# pinky_2_micro_resistors.net
KiCad netlist of a schematic drawn in EAGLE
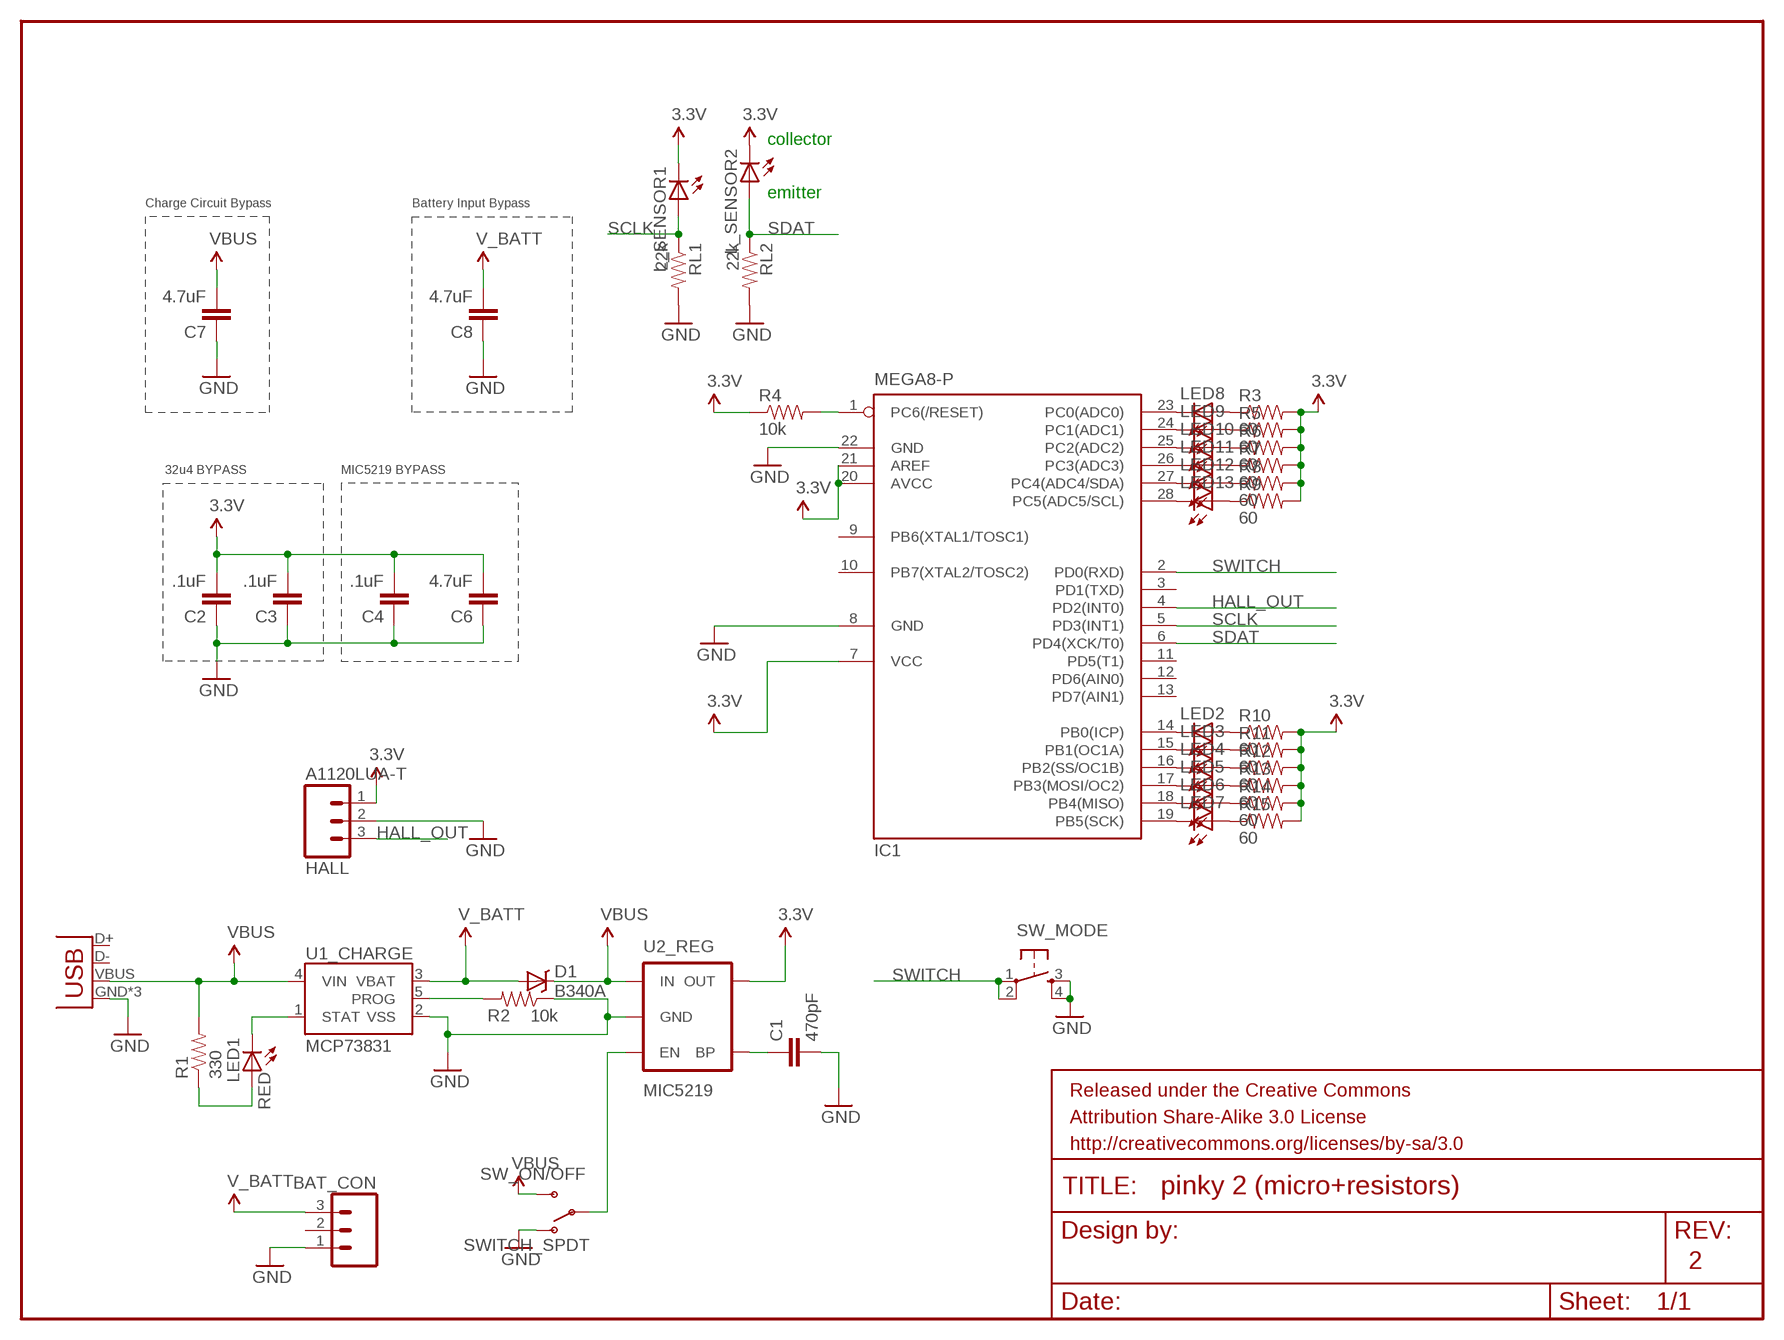
[diagram p0: schematic, sheet 1]

(export (version "E")
  (design (tool "Eeschema 10.0.6"))
  (components
    (comp (ref "BAT_CON")
      (value "M03PTH")
      (footprint "eagle-import:1X03")
      (libsource (lib "eagle-import") (part "M03PTH"))
    )
    (comp (ref "C1")
      (value "470pF")
      (footprint "eagle-import:1206")
      (libsource (lib "eagle-import") (part "CAP1206"))
    )
    (comp (ref "C2")
      (value ".1uF")
      (footprint "eagle-import:1206")
      (libsource (lib "eagle-import") (part "CAP1206"))
    )
    (comp (ref "C3")
      (value ".1uF")
      (footprint "eagle-import:1206")
      (libsource (lib "eagle-import") (part "CAP1206"))
    )
    (comp (ref "C4")
      (value ".1uF")
      (footprint "eagle-import:1206")
      (libsource (lib "eagle-import") (part "CAP1206"))
    )
    (comp (ref "C6")
      (value "4.7uF")
      (footprint "eagle-import:1206")
      (libsource (lib "eagle-import") (part "CAP1206"))
    )
    (comp (ref "C7")
      (value "4.7uF")
      (footprint "eagle-import:1206")
      (libsource (lib "eagle-import") (part "CAP1206"))
    )
    (comp (ref "C8")
      (value "4.7uF")
      (footprint "eagle-import:1206")
      (libsource (lib "eagle-import") (part "CAP1206"))
    )
    (comp (ref "D1")
      (value "B340A")
      (footprint "eagle-import:SMA-DIODE")
      (libsource (lib "eagle-import") (part "DIODE-SCHOTTKY_"))
    )
    (comp (ref "HALL")
      (value "A1120LUA-T")
      (footprint "eagle-import:1X03")
      (libsource (lib "eagle-import") (part "M03PTH"))
    )
    (comp (ref "IC1")
      (value "MEGA8-P")
      (footprint "eagle-import:DIL28-3")
      (libsource (lib "eagle-import") (part "MEGA8-P"))
    )
    (comp (ref "LED1")
      (value "RED")
      (footprint "eagle-import:LED-1206")
      (libsource (lib "eagle-import") (part "LED1206"))
    )
    (comp (ref "LED2")
      (value "LED1206")
      (footprint "eagle-import:LED-1206")
      (libsource (lib "eagle-import") (part "LED1206"))
    )
    (comp (ref "LED3")
      (value "LED1206")
      (footprint "eagle-import:LED-1206")
      (libsource (lib "eagle-import") (part "LED1206"))
    )
    (comp (ref "LED4")
      (value "LED1206")
      (footprint "eagle-import:LED-1206")
      (libsource (lib "eagle-import") (part "LED1206"))
    )
    (comp (ref "LED5")
      (value "LED1206")
      (footprint "eagle-import:LED-1206")
      (libsource (lib "eagle-import") (part "LED1206"))
    )
    (comp (ref "LED6")
      (value "LED1206")
      (footprint "eagle-import:LED-1206")
      (libsource (lib "eagle-import") (part "LED1206"))
    )
    (comp (ref "LED7")
      (value "LED1206")
      (footprint "eagle-import:LED-1206")
      (libsource (lib "eagle-import") (part "LED1206"))
    )
    (comp (ref "LED8")
      (value "LED1206")
      (footprint "eagle-import:LED-1206")
      (libsource (lib "eagle-import") (part "LED1206"))
    )
    (comp (ref "LED9")
      (value "LED1206")
      (footprint "eagle-import:LED-1206")
      (libsource (lib "eagle-import") (part "LED1206"))
    )
    (comp (ref "LED10")
      (value "LED1206")
      (footprint "eagle-import:LED-1206")
      (libsource (lib "eagle-import") (part "LED1206"))
    )
    (comp (ref "LED11")
      (value "LED1206")
      (footprint "eagle-import:LED-1206")
      (libsource (lib "eagle-import") (part "LED1206"))
    )
    (comp (ref "LED12")
      (value "LED1206")
      (footprint "eagle-import:LED-1206")
      (libsource (lib "eagle-import") (part "LED1206"))
    )
    (comp (ref "LED13")
      (value "LED1206")
      (footprint "eagle-import:LED-1206")
      (libsource (lib "eagle-import") (part "LED1206"))
    )
    (comp (ref "L_SENSOR1")
      (value "LED3MM")
      (footprint "eagle-import:LED3MM")
      (libsource (lib "eagle-import") (part "LED3MM"))
    )
    (comp (ref "L_SENSOR2")
      (value "LED3MM")
      (footprint "eagle-import:LED3MM")
      (libsource (lib "eagle-import") (part "LED3MM"))
    )
    (comp (ref "R1")
      (value "330")
      (footprint "eagle-import:1206")
      (libsource (lib "eagle-import") (part "RESISTOR1206"))
    )
    (comp (ref "R2")
      (value "10k")
      (footprint "eagle-import:1206")
      (libsource (lib "eagle-import") (part "RESISTOR1206"))
    )
    (comp (ref "R3")
      (value "60")
      (footprint "eagle-import:1206")
      (libsource (lib "eagle-import") (part "RESISTOR1206"))
    )
    (comp (ref "R4")
      (value "10k")
      (footprint "eagle-import:1206")
      (libsource (lib "eagle-import") (part "RESISTOR1206"))
    )
    (comp (ref "R5")
      (value "60")
      (footprint "eagle-import:1206")
      (libsource (lib "eagle-import") (part "RESISTOR1206"))
    )
    (comp (ref "R6")
      (value "60")
      (footprint "eagle-import:1206")
      (libsource (lib "eagle-import") (part "RESISTOR1206"))
    )
    (comp (ref "R7")
      (value "60")
      (footprint "eagle-import:1206")
      (libsource (lib "eagle-import") (part "RESISTOR1206"))
    )
    (comp (ref "R8")
      (value "60")
      (footprint "eagle-import:1206")
      (libsource (lib "eagle-import") (part "RESISTOR1206"))
    )
    (comp (ref "R9")
      (value "60")
      (footprint "eagle-import:1206")
      (libsource (lib "eagle-import") (part "RESISTOR1206"))
    )
    (comp (ref "R10")
      (value "60")
      (footprint "eagle-import:1206")
      (libsource (lib "eagle-import") (part "RESISTOR1206"))
    )
    (comp (ref "R11")
      (value "60")
      (footprint "eagle-import:1206")
      (libsource (lib "eagle-import") (part "RESISTOR1206"))
    )
    (comp (ref "R12")
      (value "60")
      (footprint "eagle-import:1206")
      (libsource (lib "eagle-import") (part "RESISTOR1206"))
    )
    (comp (ref "R13")
      (value "60")
      (footprint "eagle-import:1206")
      (libsource (lib "eagle-import") (part "RESISTOR1206"))
    )
    (comp (ref "R14")
      (value "60")
      (footprint "eagle-import:1206")
      (libsource (lib "eagle-import") (part "RESISTOR1206"))
    )
    (comp (ref "R15")
      (value "60")
      (footprint "eagle-import:1206")
      (libsource (lib "eagle-import") (part "RESISTOR1206"))
    )
    (comp (ref "RL1")
      (value "22k")
      (footprint "eagle-import:1206")
      (libsource (lib "eagle-import") (part "RESISTOR1206"))
    )
    (comp (ref "RL2")
      (value "22k")
      (footprint "eagle-import:1206")
      (libsource (lib "eagle-import") (part "RESISTOR1206"))
    )
    (comp (ref "SW_MODE")
      (value "TAC_SWITCHPTH")
      (footprint "eagle-import:TACTILE-PTH")
      (libsource (lib "eagle-import") (part "TAC_SWITCHPTH"))
    )
    (comp (ref "SW_ON/OFF")
      (value "SWITCH_SPDT")
      (footprint "eagle-import:KPS-1290")
      (libsource (lib "eagle-import") (part "SWITCH_SPDT"))
    )
    (comp (ref "U1_CHARGE")
      (value "MCP73831")
      (footprint "eagle-import:SOT23-5")
      (libsource (lib "eagle-import") (part "MCP73831"))
    )
    (comp (ref "U2_REG")
      (value "MIC5219")
      (footprint "eagle-import:SOT23-5")
      (libsource (lib "eagle-import") (part "V_REG_MIC5219SMD"))
    )
    (comp (ref "X1_USB_MICRO")
      (value "USB-MICROB")
      (footprint "eagle-import:USB-MICROB")
      (libsource (lib "eagle-import") (part "USB-MICROB"))
    )
  )
  (nets
    (net (code "1") (name "/HALL_OUT") (class "Default")
      (node (ref "HALL") (pin "3") (pinfunction "3_3") (pintype "passive"))
      (node (ref "IC1") (pin "4") (pinfunction "PD2(INT0)_4") (pintype "bidirectional"))
    )
    (net (code "2") (name "/SCLK") (class "Default")
      (node (ref "IC1") (pin "5") (pinfunction "PD3(INT1)_5") (pintype "bidirectional"))
      (node (ref "L_SENSOR1") (pin "A") (pinfunction "A_A") (pintype "passive"))
      (node (ref "RL1") (pin "1") (pinfunction "1_1") (pintype "passive"))
    )
    (net (code "3") (name "/SDAT") (class "Default")
      (node (ref "IC1") (pin "6") (pinfunction "PD4(XCK/T0)_6") (pintype "bidirectional"))
      (node (ref "L_SENSOR2") (pin "A") (pinfunction "A_A") (pintype "passive"))
      (node (ref "RL2") (pin "1") (pinfunction "1_1") (pintype "passive"))
    )
    (net (code "4") (name "/SWITCH") (class "Default")
      (node (ref "IC1") (pin "2") (pinfunction "PD0(RXD)_2") (pintype "bidirectional"))
      (node (ref "SW_MODE") (pin "1") (pinfunction "1_1") (pintype "passive"))
      (node (ref "SW_MODE") (pin "2") (pinfunction "2_2") (pintype "passive"))
    )
    (net (code "5") (name "3.3V") (class "Default")
      (node (ref "C2") (pin "2") (pinfunction "2_2") (pintype "passive"))
      (node (ref "C3") (pin "2") (pinfunction "2_2") (pintype "passive"))
      (node (ref "C4") (pin "2") (pinfunction "2_2") (pintype "passive"))
      (node (ref "C6") (pin "2") (pinfunction "2_2") (pintype "passive"))
      (node (ref "HALL") (pin "1") (pinfunction "1_1") (pintype "passive"))
      (node (ref "IC1") (pin "20") (pinfunction "AVCC_20") (pintype "power_in"))
      (node (ref "IC1") (pin "21") (pinfunction "AREF_21") (pintype "passive"))
      (node (ref "IC1") (pin "7") (pinfunction "VCC_7") (pintype "power_in"))
      (node (ref "L_SENSOR1") (pin "K") (pinfunction "C_K") (pintype "passive"))
      (node (ref "L_SENSOR2") (pin "K") (pinfunction "C_K") (pintype "passive"))
      (node (ref "R10") (pin "2") (pinfunction "2_2") (pintype "passive"))
      (node (ref "R11") (pin "2") (pinfunction "2_2") (pintype "passive"))
      (node (ref "R12") (pin "2") (pinfunction "2_2") (pintype "passive"))
      (node (ref "R13") (pin "2") (pinfunction "2_2") (pintype "passive"))
      (node (ref "R14") (pin "2") (pinfunction "2_2") (pintype "passive"))
      (node (ref "R15") (pin "2") (pinfunction "2_2") (pintype "passive"))
      (node (ref "R3") (pin "2") (pinfunction "2_2") (pintype "passive"))
      (node (ref "R4") (pin "1") (pinfunction "1_1") (pintype "passive"))
      (node (ref "R5") (pin "2") (pinfunction "2_2") (pintype "passive"))
      (node (ref "R6") (pin "2") (pinfunction "2_2") (pintype "passive"))
      (node (ref "R7") (pin "2") (pinfunction "2_2") (pintype "passive"))
      (node (ref "R8") (pin "2") (pinfunction "2_2") (pintype "passive"))
      (node (ref "R9") (pin "2") (pinfunction "2_2") (pintype "passive"))
      (node (ref "U2_REG") (pin "5") (pinfunction "OUT_5") (pintype "passive"))
    )
    (net (code "6") (name "GND") (class "Default")
      (node (ref "BAT_CON") (pin "1") (pinfunction "1_1") (pintype "passive"))
      (node (ref "C1") (pin "2") (pinfunction "2_2") (pintype "passive"))
      (node (ref "C2") (pin "1") (pinfunction "1_1") (pintype "passive"))
      (node (ref "C3") (pin "1") (pinfunction "1_1") (pintype "passive"))
      (node (ref "C4") (pin "1") (pinfunction "1_1") (pintype "passive"))
      (node (ref "C6") (pin "1") (pinfunction "1_1") (pintype "passive"))
      (node (ref "C7") (pin "1") (pinfunction "1_1") (pintype "passive"))
      (node (ref "C8") (pin "1") (pinfunction "1_1") (pintype "passive"))
      (node (ref "HALL") (pin "2") (pinfunction "2_2") (pintype "passive"))
      (node (ref "IC1") (pin "22") (pinfunction "GND_22") (pintype "power_in"))
      (node (ref "IC1") (pin "8") (pinfunction "GND_8") (pintype "power_in"))
      (node (ref "R2") (pin "1") (pinfunction "1_1") (pintype "passive"))
      (node (ref "RL1") (pin "2") (pinfunction "2_2") (pintype "passive"))
      (node (ref "RL2") (pin "2") (pinfunction "2_2") (pintype "passive"))
      (node (ref "SW_MODE") (pin "3") (pinfunction "3_3") (pintype "passive"))
      (node (ref "SW_MODE") (pin "4") (pinfunction "4_4") (pintype "passive"))
      (node (ref "SW_ON/OFF") (pin "O") (pinfunction "O_O") (pintype "passive"))
      (node (ref "U1_CHARGE") (pin "2") (pinfunction "VSS_2") (pintype "power_in"))
      (node (ref "U2_REG") (pin "2") (pinfunction "GND_2") (pintype "input"))
      (node (ref "X1_USB_MICRO") (pin "GND") (pinfunction "GND_GND") (pintype "bidirectional"))
      (node (ref "X1_USB_MICRO") (pin "MT1") (pinfunction "GND_MT1") (pintype "bidirectional"))
      (node (ref "X1_USB_MICRO") (pin "MT2") (pinfunction "GND_MT2") (pintype "bidirectional"))
    )
    (net (code "7") (name "Net-(IC1-PB0(ICP))") (class "Default")
      (node (ref "IC1") (pin "14") (pinfunction "PB0(ICP)_14") (pintype "bidirectional"))
      (node (ref "LED2") (pin "C") (pinfunction "C_C") (pintype "passive"))
    )
    (net (code "8") (name "Net-(IC1-PB1(OC1A))") (class "Default")
      (node (ref "IC1") (pin "15") (pinfunction "PB1(OC1A)_15") (pintype "bidirectional"))
      (node (ref "LED3") (pin "C") (pinfunction "C_C") (pintype "passive"))
    )
    (net (code "9") (name "Net-(IC1-PB2(SS{slash}OC1B))") (class "Default")
      (node (ref "IC1") (pin "16") (pinfunction "PB2(SS/OC1B)_16") (pintype "bidirectional"))
      (node (ref "LED4") (pin "C") (pinfunction "C_C") (pintype "passive"))
    )
    (net (code "10") (name "Net-(IC1-PB3(MOSI{slash}OC2))") (class "Default")
      (node (ref "IC1") (pin "17") (pinfunction "PB3(MOSI/OC2)_17") (pintype "bidirectional"))
      (node (ref "LED5") (pin "C") (pinfunction "C_C") (pintype "passive"))
    )
    (net (code "11") (name "Net-(IC1-PB4(MISO))") (class "Default")
      (node (ref "IC1") (pin "18") (pinfunction "PB4(MISO)_18") (pintype "bidirectional"))
      (node (ref "LED6") (pin "C") (pinfunction "C_C") (pintype "passive"))
    )
    (net (code "12") (name "Net-(IC1-PB5(SCK))") (class "Default")
      (node (ref "IC1") (pin "19") (pinfunction "PB5(SCK)_19") (pintype "bidirectional"))
      (node (ref "LED7") (pin "C") (pinfunction "C_C") (pintype "passive"))
    )
    (net (code "13") (name "Net-(IC1-PC0(ADC0))") (class "Default")
      (node (ref "IC1") (pin "23") (pinfunction "PC0(ADC0)_23") (pintype "bidirectional"))
      (node (ref "LED8") (pin "C") (pinfunction "C_C") (pintype "passive"))
    )
    (net (code "14") (name "Net-(IC1-PC1(ADC1))") (class "Default")
      (node (ref "IC1") (pin "24") (pinfunction "PC1(ADC1)_24") (pintype "bidirectional"))
      (node (ref "LED9") (pin "C") (pinfunction "C_C") (pintype "passive"))
    )
    (net (code "15") (name "Net-(IC1-PC2(ADC2))") (class "Default")
      (node (ref "IC1") (pin "25") (pinfunction "PC2(ADC2)_25") (pintype "bidirectional"))
      (node (ref "LED10") (pin "C") (pinfunction "C_C") (pintype "passive"))
    )
    (net (code "16") (name "Net-(IC1-PC3(ADC3))") (class "Default")
      (node (ref "IC1") (pin "26") (pinfunction "PC3(ADC3)_26") (pintype "bidirectional"))
      (node (ref "LED11") (pin "C") (pinfunction "C_C") (pintype "passive"))
    )
    (net (code "17") (name "Net-(IC1-PC4(ADC4{slash}SDA))") (class "Default")
      (node (ref "IC1") (pin "27") (pinfunction "PC4(ADC4/SDA)_27") (pintype "bidirectional"))
      (node (ref "LED12") (pin "C") (pinfunction "C_C") (pintype "passive"))
    )
    (net (code "18") (name "Net-(IC1-PC5(ADC5{slash}SCL))") (class "Default")
      (node (ref "IC1") (pin "28") (pinfunction "PC5(ADC5/SCL)_28") (pintype "bidirectional"))
      (node (ref "LED13") (pin "C") (pinfunction "C_C") (pintype "passive"))
    )
    (net (code "19") (name "Net-(IC1-PC6({slash}RESET))") (class "Default")
      (node (ref "IC1") (pin "1") (pinfunction "PC6(/RESET)_1") (pintype "bidirectional"))
      (node (ref "R4") (pin "2") (pinfunction "2_2") (pintype "passive"))
    )
    (net (code "20") (name "Net-(LED1-PadA)") (class "Default")
      (node (ref "LED1") (pin "A") (pinfunction "A_A") (pintype "passive"))
      (node (ref "R1") (pin "1") (pinfunction "1_1") (pintype "passive"))
    )
    (net (code "21") (name "Net-(LED2-PadA)") (class "Default")
      (node (ref "LED2") (pin "A") (pinfunction "A_A") (pintype "passive"))
      (node (ref "R10") (pin "1") (pinfunction "1_1") (pintype "passive"))
    )
    (net (code "22") (name "Net-(LED3-PadA)") (class "Default")
      (node (ref "LED3") (pin "A") (pinfunction "A_A") (pintype "passive"))
      (node (ref "R11") (pin "1") (pinfunction "1_1") (pintype "passive"))
    )
    (net (code "23") (name "Net-(LED4-PadA)") (class "Default")
      (node (ref "LED4") (pin "A") (pinfunction "A_A") (pintype "passive"))
      (node (ref "R12") (pin "1") (pinfunction "1_1") (pintype "passive"))
    )
    (net (code "24") (name "Net-(LED5-PadA)") (class "Default")
      (node (ref "LED5") (pin "A") (pinfunction "A_A") (pintype "passive"))
      (node (ref "R13") (pin "1") (pinfunction "1_1") (pintype "passive"))
    )
    (net (code "25") (name "Net-(LED6-PadA)") (class "Default")
      (node (ref "LED6") (pin "A") (pinfunction "A_A") (pintype "passive"))
      (node (ref "R14") (pin "1") (pinfunction "1_1") (pintype "passive"))
    )
    (net (code "26") (name "Net-(LED7-PadA)") (class "Default")
      (node (ref "LED7") (pin "A") (pinfunction "A_A") (pintype "passive"))
      (node (ref "R15") (pin "1") (pinfunction "1_1") (pintype "passive"))
    )
    (net (code "27") (name "Net-(LED8-PadA)") (class "Default")
      (node (ref "LED8") (pin "A") (pinfunction "A_A") (pintype "passive"))
      (node (ref "R3") (pin "1") (pinfunction "1_1") (pintype "passive"))
    )
    (net (code "28") (name "Net-(LED9-PadA)") (class "Default")
      (node (ref "LED9") (pin "A") (pinfunction "A_A") (pintype "passive"))
      (node (ref "R5") (pin "1") (pinfunction "1_1") (pintype "passive"))
    )
    (net (code "29") (name "Net-(LED10-PadA)") (class "Default")
      (node (ref "LED10") (pin "A") (pinfunction "A_A") (pintype "passive"))
      (node (ref "R6") (pin "1") (pinfunction "1_1") (pintype "passive"))
    )
    (net (code "30") (name "Net-(LED11-PadA)") (class "Default")
      (node (ref "LED11") (pin "A") (pinfunction "A_A") (pintype "passive"))
      (node (ref "R7") (pin "1") (pinfunction "1_1") (pintype "passive"))
    )
    (net (code "31") (name "Net-(LED12-PadA)") (class "Default")
      (node (ref "LED12") (pin "A") (pinfunction "A_A") (pintype "passive"))
      (node (ref "R8") (pin "1") (pinfunction "1_1") (pintype "passive"))
    )
    (net (code "32") (name "Net-(LED13-PadA)") (class "Default")
      (node (ref "LED13") (pin "A") (pinfunction "A_A") (pintype "passive"))
      (node (ref "R9") (pin "1") (pinfunction "1_1") (pintype "passive"))
    )
    (net (code "33") (name "Net-(U1_CHARGE-PROG)") (class "Default")
      (node (ref "R2") (pin "2") (pinfunction "2_2") (pintype "passive"))
      (node (ref "U1_CHARGE") (pin "5") (pinfunction "PROG_5") (pintype "input"))
    )
    (net (code "34") (name "Net-(U1_CHARGE-STAT)") (class "Default")
      (node (ref "LED1") (pin "C") (pinfunction "C_C") (pintype "passive"))
      (node (ref "U1_CHARGE") (pin "1") (pinfunction "STAT_1") (pintype "output"))
    )
    (net (code "35") (name "Net-(U2_REG-BP)") (class "Default")
      (node (ref "C1") (pin "1") (pinfunction "1_1") (pintype "passive"))
      (node (ref "U2_REG") (pin "4") (pinfunction "BP_4") (pintype "input"))
    )
    (net (code "36") (name "Net-(U2_REG-EN)") (class "Default")
      (node (ref "SW_ON/OFF") (pin "P") (pinfunction "P_P") (pintype "passive"))
      (node (ref "U2_REG") (pin "3") (pinfunction "EN_3") (pintype "input"))
    )
    (net (code "37") (name "VBUS") (class "Default")
      (node (ref "C7") (pin "2") (pinfunction "2_2") (pintype "passive"))
      (node (ref "D1") (pin "C") (pinfunction "C_C") (pintype "passive"))
      (node (ref "R1") (pin "2") (pinfunction "2_2") (pintype "passive"))
      (node (ref "SW_ON/OFF") (pin "S") (pinfunction "S_S") (pintype "passive"))
      (node (ref "U1_CHARGE") (pin "4") (pinfunction "VIN_4") (pintype "power_in"))
      (node (ref "U2_REG") (pin "1") (pinfunction "IN_1") (pintype "input"))
      (node (ref "X1_USB_MICRO") (pin "VBUS") (pinfunction "VBUS_VBUS") (pintype "bidirectional"))
    )
    (net (code "38") (name "V_BATT") (class "Default")
      (node (ref "BAT_CON") (pin "3") (pinfunction "3_3") (pintype "passive"))
      (node (ref "C8") (pin "2") (pinfunction "2_2") (pintype "passive"))
      (node (ref "D1") (pin "A") (pinfunction "A_A") (pintype "passive"))
      (node (ref "U1_CHARGE") (pin "3") (pinfunction "VBAT_3") (pintype "power_in"))
    )
    (net (code "39") (name "unconnected-(BAT_CON-Pad2)") (class "Default")
      (node (ref "BAT_CON") (pin "2") (pinfunction "2_2") (pintype "passive"))
    )
    (net (code "40") (name "unconnected-(IC1-PB6(XTAL1{slash}TOSC1)-Pad9)") (class "Default")
      (node (ref "IC1") (pin "9") (pinfunction "PB6(XTAL1/TOSC1)_9") (pintype "bidirectional"))
    )
    (net (code "41") (name "unconnected-(IC1-PB7(XTAL2{slash}TOSC2)-Pad10)") (class "Default")
      (node (ref "IC1") (pin "10") (pinfunction "PB7(XTAL2/TOSC2)_10") (pintype "bidirectional"))
    )
    (net (code "42") (name "unconnected-(IC1-PD1(TXD)-Pad3)") (class "Default")
      (node (ref "IC1") (pin "3") (pinfunction "PD1(TXD)_3") (pintype "bidirectional"))
    )
    (net (code "43") (name "unconnected-(IC1-PD5(T1)-Pad11)") (class "Default")
      (node (ref "IC1") (pin "11") (pinfunction "PD5(T1)_11") (pintype "bidirectional"))
    )
    (net (code "44") (name "unconnected-(IC1-PD6(AIN0)-Pad12)") (class "Default")
      (node (ref "IC1") (pin "12") (pinfunction "PD6(AIN0)_12") (pintype "bidirectional"))
    )
    (net (code "45") (name "unconnected-(IC1-PD7(AIN1)-Pad13)") (class "Default")
      (node (ref "IC1") (pin "13") (pinfunction "PD7(AIN1)_13") (pintype "bidirectional"))
    )
    (net (code "46") (name "unconnected-(X1_USB_MICRO-PadD+)") (class "Default")
      (node (ref "X1_USB_MICRO") (pin "D+") (pinfunction "D+_D+") (pintype "bidirectional"))
    )
    (net (code "47") (name "unconnected-(X1_USB_MICRO-PadD-)") (class "Default")
      (node (ref "X1_USB_MICRO") (pin "D-") (pinfunction "D-_D-") (pintype "bidirectional"))
    )
  )
)
